# OpenPLCv0_2_0_Watchdog.net
KiCad netlist of a schematic drawn in Altium Designer
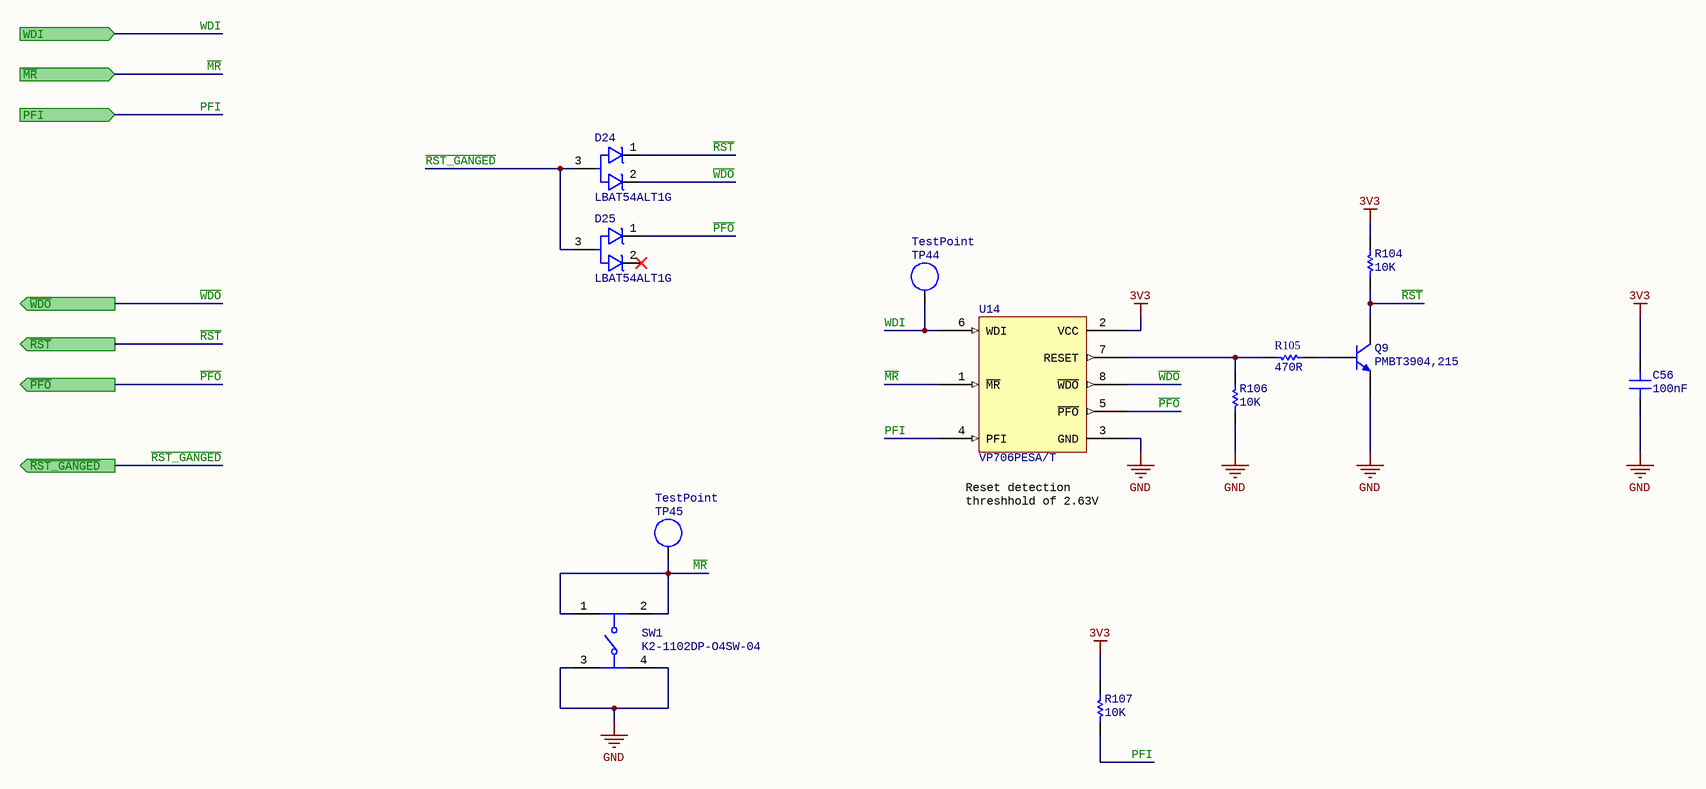
[diagram p0: OpenPLCv0.2.0_Watchdog.SchDoc]

(export (version "E")
  (design (tool "Eeschema 10.0.6"))
  (components
    (comp (ref "C56")
      (value "CC0402KRX5R6BB104")
      (footprint "SMD_CAP_0402(1005)_N")
      (description "100nF ±10% 10V X5R 0402 Multilayer Ceramic Capacitors MLCC - SMD/SMT RoHS")
      (fields (field (name "TOLERANCE") "10%") (field (name "CAPACITANCE") "100nF"))
      (libsource (lib "BrauV2_Capacitor") (part "100nF 0402 10V 10%"))
    )
    (comp (ref "D24")
      (value "LBAT54ALT1G")
      (footprint "SOT23-3")
      (description "30V 200mA 320mV @ 1mA SOT-23(SOT-23-3) Schottky Barrier Diodes (SBD) RoHS")
      (libsource (lib "BrauV2_Diode") (part "LBAT54ALT1G"))
    )
    (comp (ref "D25")
      (value "LBAT54ALT1G")
      (footprint "SOT23-3")
      (description "30V 200mA 320mV @ 1mA SOT-23(SOT-23-3) Schottky Barrier Diodes (SBD) RoHS")
      (libsource (lib "BrauV2_Diode") (part "LBAT54ALT1G"))
    )
    (comp (ref "Q9")
      (value "PMBT3904,215")
      (footprint "SOT23-3")
      (description "NPN 200mA 40V 250mW SOT-23(SOT-23-3) Transistors (NPN/PNP) RoHS")
      (libsource (lib "BrauV2_Transistor") (part "PMBT3904,215"))
    )
    (comp (ref "R104")
      (value "RC0402FR-0710KL")
      (footprint "SMD_RES_0402(1005)_N")
      (description "10kΩ ±1% 1/16W ±100ppm/℃ 0402 Chip Resistor - Surface Mount RoHS")
      (fields (field (name "TOLERANCE") "1%") (field (name "RESISTANCE") "10K"))
      (libsource (lib "BrauV2_Resistor") (part "10K 0402 1% 1/16W"))
    )
    (comp (ref "R105")
      (value "RC0402FR-07470RL")
      (footprint "SMD_RES_0402(1005)_N")
      (description "470Ω ±1% 1/16W ±100ppm/℃ 0402 Chip Resistor - Surface Mount RoHS")
      (fields (field (name "TOLERANCE") "1%") (field (name "RESISTANCE") "470R"))
      (libsource (lib "BrauV2_Resistor") (part "470R 0402 1% 1W"))
    )
    (comp (ref "R106")
      (value "RC0402FR-0710KL")
      (footprint "SMD_RES_0402(1005)_N")
      (description "10kΩ ±1% 1/16W ±100ppm/℃ 0402 Chip Resistor - Surface Mount RoHS")
      (fields (field (name "TOLERANCE") "1%") (field (name "RESISTANCE") "10K"))
      (libsource (lib "BrauV2_Resistor") (part "10K 0402 1% 1/16W"))
    )
    (comp (ref "R107")
      (value "RC0402FR-0710KL")
      (footprint "SMD_RES_0402(1005)_N")
      (description "10kΩ ±1% 1/16W ±100ppm/℃ 0402 Chip Resistor - Surface Mount RoHS")
      (fields (field (name "TOLERANCE") "1%") (field (name "RESISTANCE") "10K"))
      (libsource (lib "BrauV2_Resistor") (part "10K 0402 1% 1/16W"))
    )
    (comp (ref "SW1")
      (value "K2-1102DP-O4SW-04")
      (footprint "K2-1102DP-O4SW-04")
      (description "6x6x11mm Through Hole Tactile Switches ROHS")
      (libsource (lib "BrauV2_Misc") (part "K2-1102DP-O4SW-04"))
    )
    (comp (ref "TP44")
      (value "TestPoint")
      (footprint "Pad")
      (libsource (lib "OpenPLCv0.2.0_Misc") (part "Test point"))
    )
    (comp (ref "TP45")
      (value "TestPoint")
      (footprint "Pad")
      (libsource (lib "OpenPLCv0.2.0_Misc") (part "Test point"))
    )
    (comp (ref "U14")
      (value "VP706PESA/T")
      (footprint "SOIC-8-3.9mm")
      (description "SIOC-8 Monitors & Reset Circuits ROHS, 2.63V, -40°C to 85°C (copy of MAX706P)")
      (libsource (lib "BrauV2_IC") (part "VP706PESA/T"))
    )
  )
  (nets
    (net (code "1") (name "/PFI") (class "Default")
      (node (ref "R107") (pin "1") (pinfunction "1_1") (pintype "passive"))
      (node (ref "U14") (pin "4") (pinfunction "PFI_4") (pintype "input"))
    )
    (net (code "2") (name "/WDI") (class "Default")
      (node (ref "TP44") (pin "1") (pinfunction "1_1") (pintype "passive"))
      (node (ref "U14") (pin "6") (pinfunction "WDI_6") (pintype "input"))
    )
    (net (code "3") (name "/~{MR}") (class "Default")
      (node (ref "SW1") (pin "1") (pinfunction "1_1") (pintype "passive"))
      (node (ref "SW1") (pin "2") (pinfunction "2_2") (pintype "passive"))
      (node (ref "TP45") (pin "1") (pinfunction "1_1") (pintype "passive"))
      (node (ref "U14") (pin "1") (pinfunction "~{MR}_1") (pintype "input"))
    )
    (net (code "4") (name "/~{PFO}") (class "Default")
      (node (ref "D25") (pin "1") (pinfunction "CATHODE_1") (pintype "passive"))
      (node (ref "U14") (pin "5") (pinfunction "~{PFO}_5") (pintype "output"))
    )
    (net (code "5") (name "/~{RST_GANGED}") (class "Default")
      (node (ref "D24") (pin "3") (pinfunction "ANODE_3") (pintype "passive"))
      (node (ref "D25") (pin "3") (pinfunction "ANODE_3") (pintype "passive"))
    )
    (net (code "6") (name "/~{RST}") (class "Default")
      (node (ref "D24") (pin "1") (pinfunction "CATHODE_1") (pintype "passive"))
      (node (ref "Q9") (pin "3") (pinfunction "C_3") (pintype "passive"))
      (node (ref "R104") (pin "1") (pinfunction "1_1") (pintype "passive"))
    )
    (net (code "7") (name "/~{WDO}") (class "Default")
      (node (ref "D24") (pin "2") (pinfunction "CATHODE_2") (pintype "passive"))
      (node (ref "U14") (pin "8") (pinfunction "~{WDO}_8") (pintype "output"))
    )
    (net (code "8") (name "3V3") (class "Default")
      (node (ref "C56") (pin "2") (pinfunction "2_2") (pintype "passive"))
      (node (ref "R104") (pin "2") (pinfunction "2_2") (pintype "passive"))
      (node (ref "R107") (pin "2") (pinfunction "2_2") (pintype "passive"))
      (node (ref "U14") (pin "2") (pinfunction "VCC_2") (pintype "power_in"))
    )
    (net (code "9") (name "GND") (class "Default")
      (node (ref "C56") (pin "1") (pinfunction "1_1") (pintype "passive"))
      (node (ref "Q9") (pin "2") (pinfunction "E_2") (pintype "passive"))
      (node (ref "R106") (pin "1") (pinfunction "1_1") (pintype "passive"))
      (node (ref "SW1") (pin "3") (pinfunction "3_3") (pintype "passive"))
      (node (ref "SW1") (pin "4") (pinfunction "4_4") (pintype "passive"))
      (node (ref "U14") (pin "3") (pinfunction "GND_3") (pintype "power_in"))
    )
    (net (code "10") (name "Net-(Q9-B)") (class "Default")
      (node (ref "Q9") (pin "1") (pinfunction "B_1") (pintype "passive"))
      (node (ref "R105") (pin "2") (pinfunction "2_2") (pintype "passive"))
    )
    (net (code "11") (name "Net-(U14-RESET)") (class "Default")
      (node (ref "R105") (pin "1") (pinfunction "1_1") (pintype "passive"))
      (node (ref "R106") (pin "2") (pinfunction "2_2") (pintype "passive"))
      (node (ref "U14") (pin "7") (pinfunction "RESET_7") (pintype "output"))
    )
    (net (code "12") (name "unconnected-(D25-CATHODE-Pad2)") (class "Default")
      (node (ref "D25") (pin "2") (pinfunction "CATHODE_2") (pintype "passive+no_connect"))
    )
  )
)
